# SCH__copy_2024-03-07.net
KiCad netlist of a schematic drawn in EasyEDA
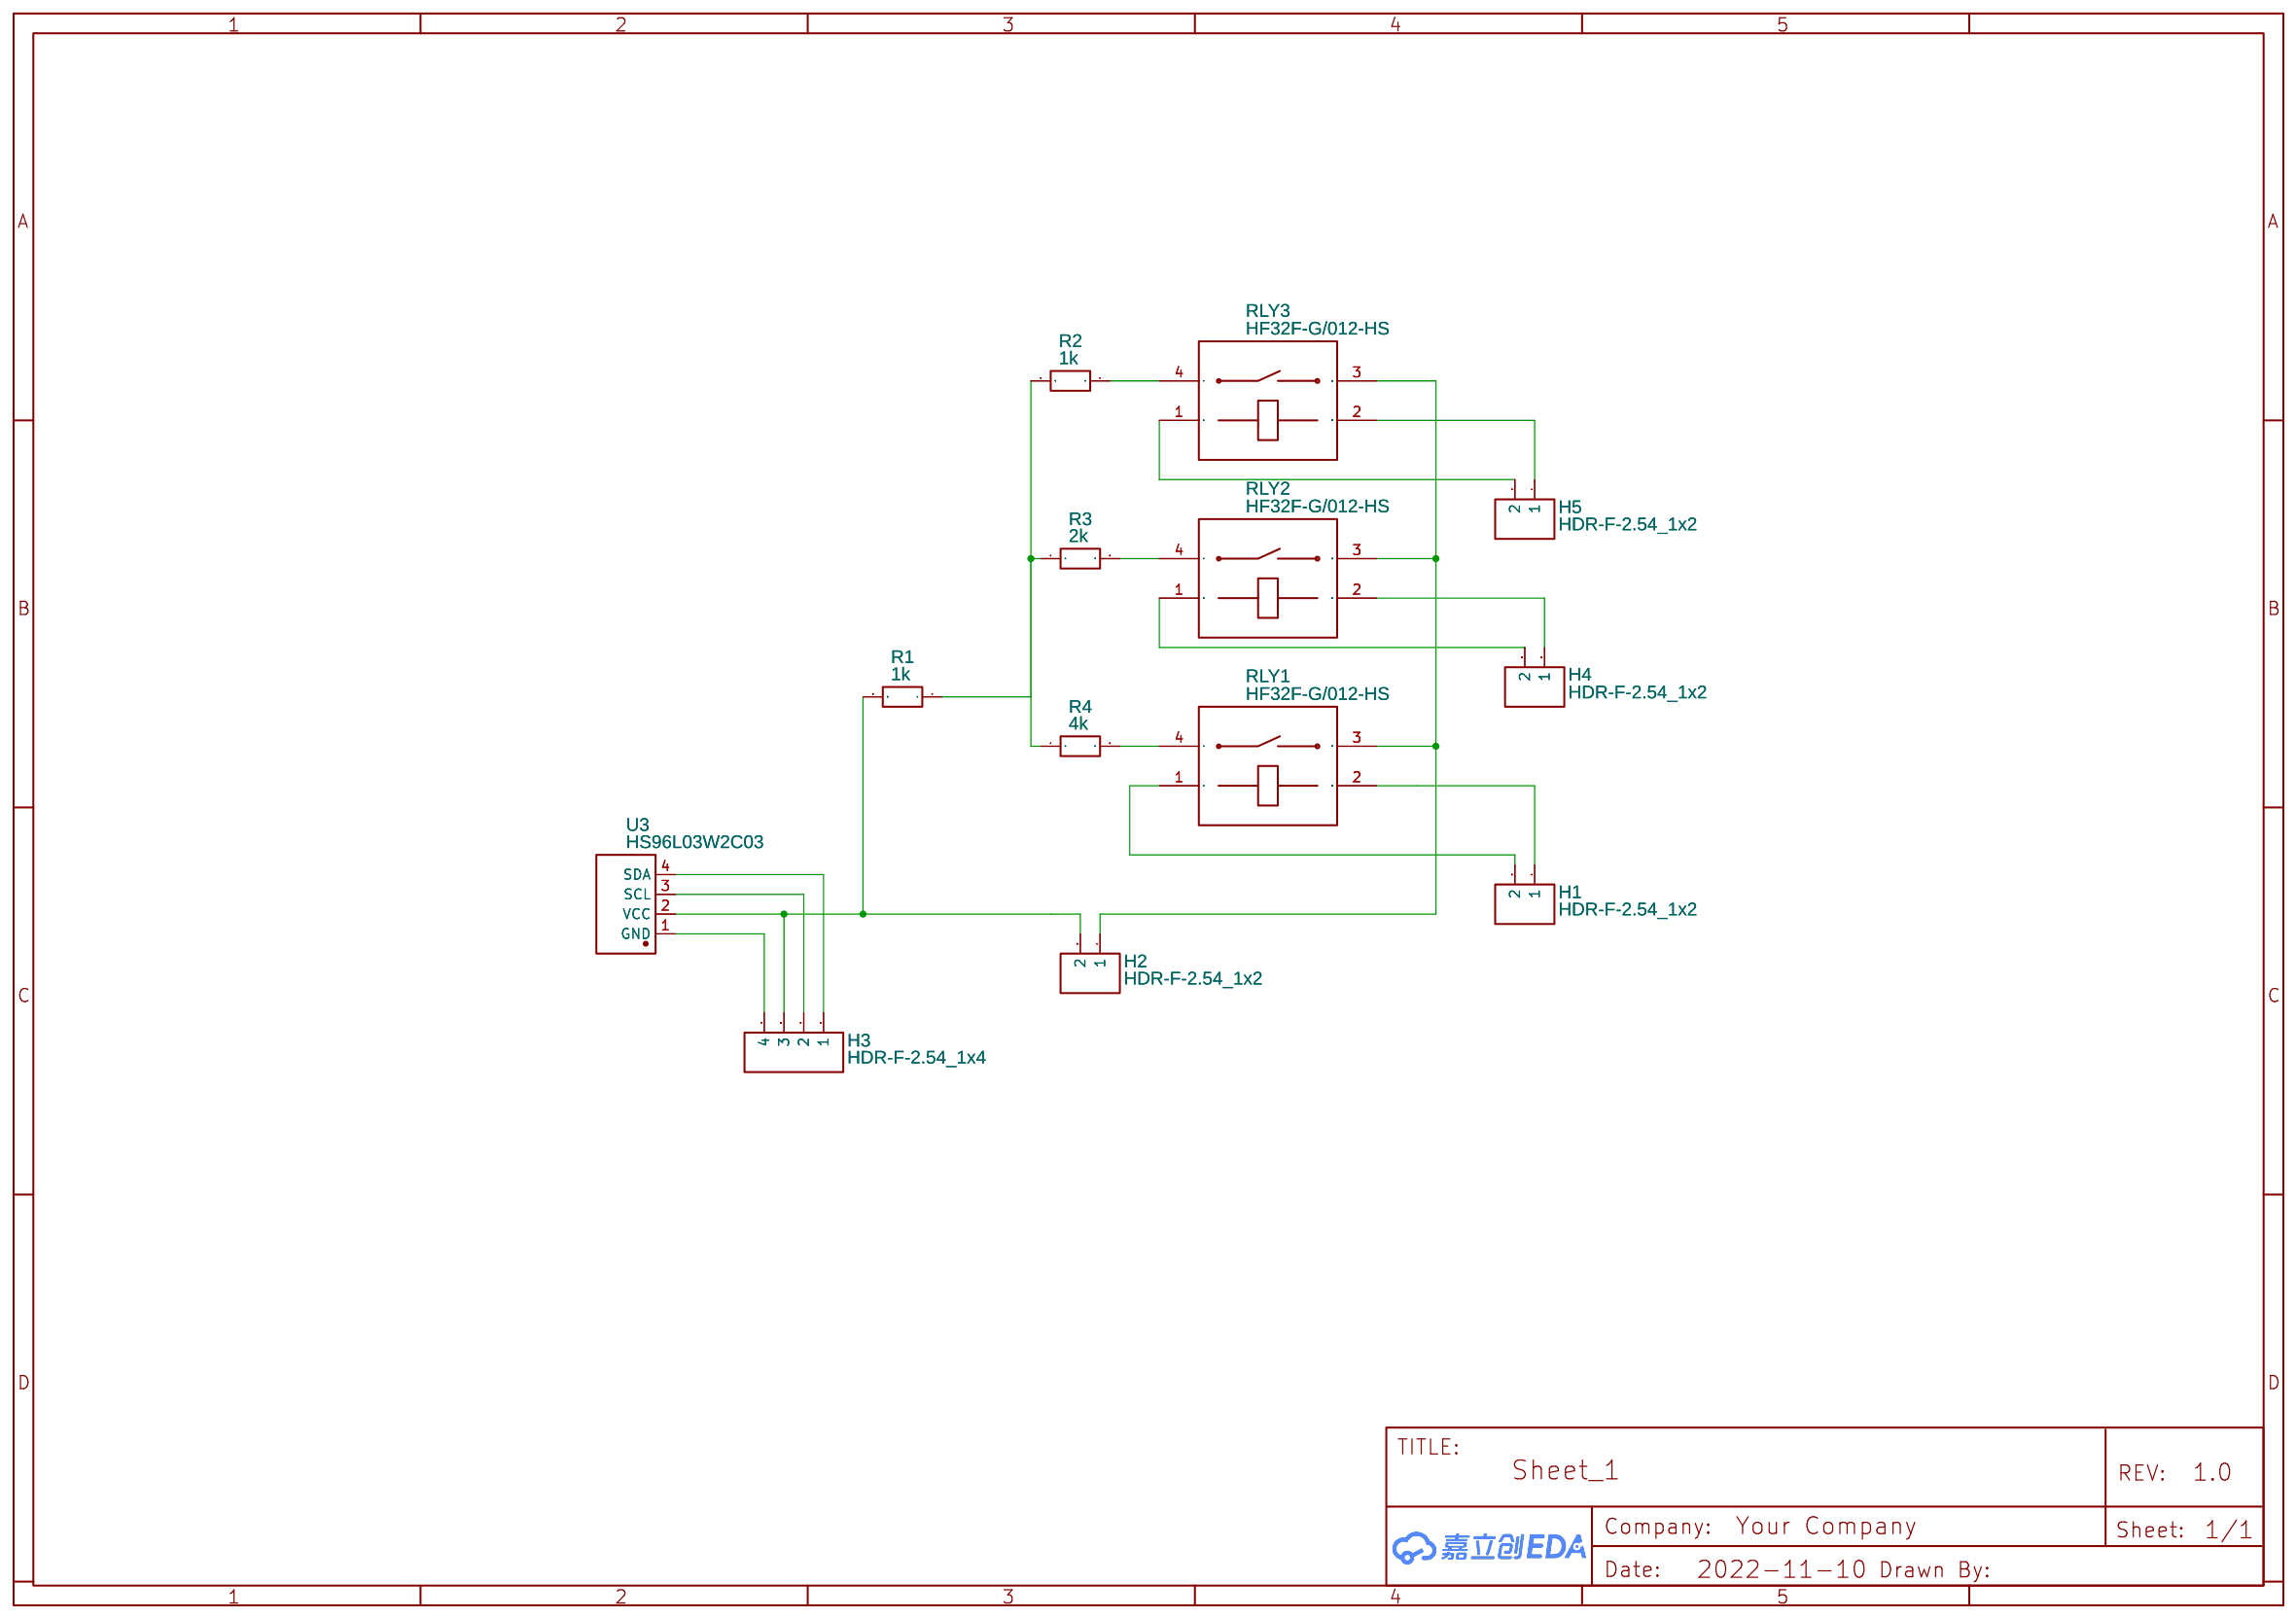
[diagram p0: schematic sheet]

(export (version "E")
  (design (tool "Eeschema 10.0.6"))
  (components
    (comp (ref "H1")
      (value "HDR-F-2.54_1x2")
      (fields (field (name "BOM_Supplier Part") "C49661"))
      (libsource (lib "") (part "HDR-F-2.54_1x2"))
    )
    (comp (ref "H2")
      (value "HDR-F-2.54_1x2")
      (fields (field (name "BOM_Supplier Part") "C49661"))
      (libsource (lib "") (part "HDR-F-2.54_1x2"))
    )
    (comp (ref "H3")
      (value "HDR-F-2.54_1x4")
      (fields (field (name "BOM_Supplier Part") "C225501"))
      (libsource (lib "") (part "HDR-F-2.54_1x4"))
    )
    (comp (ref "H4")
      (value "HDR-F-2.54_1x2")
      (fields (field (name "BOM_Supplier Part") "C49661"))
      (libsource (lib "") (part "HDR-F-2.54_1x2"))
    )
    (comp (ref "H5")
      (value "HDR-F-2.54_1x2")
      (fields (field (name "BOM_Supplier Part") "C49661"))
      (libsource (lib "") (part "HDR-F-2.54_1x2"))
    )
    (comp (ref "R1") (value "1k") (libsource (lib "") (part "R_AXIAL-0.3_EU")))
    (comp (ref "R2") (value "1k") (libsource (lib "") (part "R_AXIAL-0.3_EU")))
    (comp (ref "R3") (value "2k") (libsource (lib "") (part "R_0603_EU")))
    (comp (ref "R4") (value "4k") (libsource (lib "") (part "R_0603_EU")))
    (comp (ref "RLY1")
      (value "HF32F-G/012-HS")
      (fields (field (name "BOM_Supplier Part") "C53562"))
      (libsource (lib "") (part "HF32F-G/012-HS"))
    )
    (comp (ref "RLY2")
      (value "HF32F-G/012-HS")
      (fields (field (name "BOM_Supplier Part") "C53562"))
      (libsource (lib "") (part "HF32F-G/012-HS"))
    )
    (comp (ref "RLY3")
      (value "HF32F-G/012-HS")
      (fields (field (name "BOM_Supplier Part") "C53562"))
      (libsource (lib "") (part "HF32F-G/012-HS"))
    )
    (comp (ref "U3")
      (value "HS96L03W2C03")
      (fields (field (name "BOM_Supplier Part") "C5248080"))
      (libsource (lib "") (part "HS96L03W2C03"))
    )
  )
  (nets
    (net (code "1") (name "Net-(H1-Pad1)") (class "Default")
      (node (ref "H1") (pin "1") (pinfunction "1_1") (pintype "input"))
      (node (ref "RLY1") (pin "2") (pinfunction "2_2") (pintype "input"))
    )
    (net (code "2") (name "Net-(H1-Pad2)") (class "Default")
      (node (ref "H1") (pin "2") (pinfunction "2_2") (pintype "input"))
      (node (ref "RLY1") (pin "1") (pinfunction "1_1") (pintype "input"))
    )
    (net (code "3") (name "Net-(H2-Pad1)") (class "Default")
      (node (ref "H2") (pin "1") (pinfunction "1_1") (pintype "input"))
      (node (ref "RLY1") (pin "3") (pinfunction "3_3") (pintype "input"))
      (node (ref "RLY2") (pin "3") (pinfunction "3_3") (pintype "input"))
      (node (ref "RLY3") (pin "3") (pinfunction "3_3") (pintype "input"))
    )
    (net (code "4") (name "Net-(H4-Pad1)") (class "Default")
      (node (ref "H4") (pin "1") (pinfunction "1_1") (pintype "input"))
      (node (ref "RLY2") (pin "2") (pinfunction "2_2") (pintype "input"))
    )
    (net (code "5") (name "Net-(H4-Pad2)") (class "Default")
      (node (ref "H4") (pin "2") (pinfunction "2_2") (pintype "input"))
      (node (ref "RLY2") (pin "1") (pinfunction "1_1") (pintype "input"))
    )
    (net (code "6") (name "Net-(H5-Pad1)") (class "Default")
      (node (ref "H5") (pin "1") (pinfunction "1_1") (pintype "input"))
      (node (ref "RLY3") (pin "2") (pinfunction "2_2") (pintype "input"))
    )
    (net (code "7") (name "Net-(H5-Pad2)") (class "Default")
      (node (ref "H5") (pin "2") (pinfunction "2_2") (pintype "input"))
      (node (ref "RLY3") (pin "1") (pinfunction "1_1") (pintype "input"))
    )
    (net (code "8") (name "Net-(R1-Pad1)") (class "Default")
      (node (ref "R1") (pin "1") (pinfunction "1_1") (pintype "unspecified"))
      (node (ref "R2") (pin "2") (pinfunction "2_2") (pintype "unspecified"))
      (node (ref "R3") (pin "1") (pinfunction "1_1") (pintype "unspecified"))
      (node (ref "R4") (pin "1") (pinfunction "1_1") (pintype "unspecified"))
    )
    (net (code "9") (name "Net-(R2-Pad1)") (class "Default")
      (node (ref "R2") (pin "1") (pinfunction "1_1") (pintype "unspecified"))
      (node (ref "RLY3") (pin "4") (pinfunction "4_4") (pintype "input"))
    )
    (net (code "10") (name "Net-(R3-Pad2)") (class "Default")
      (node (ref "R3") (pin "2") (pinfunction "2_2") (pintype "unspecified"))
      (node (ref "RLY2") (pin "4") (pinfunction "4_4") (pintype "input"))
    )
    (net (code "11") (name "Net-(R4-Pad2)") (class "Default")
      (node (ref "R4") (pin "2") (pinfunction "2_2") (pintype "unspecified"))
      (node (ref "RLY1") (pin "4") (pinfunction "4_4") (pintype "input"))
    )
    (net (code "12") (name "Net-(U3-GND)") (class "Default")
      (node (ref "H3") (pin "4") (pinfunction "4_4") (pintype "unspecified"))
      (node (ref "U3") (pin "1") (pinfunction "GND_1") (pintype "unspecified"))
    )
    (net (code "13") (name "Net-(U3-SCL)") (class "Default")
      (node (ref "H3") (pin "2") (pinfunction "2_2") (pintype "unspecified"))
      (node (ref "U3") (pin "3") (pinfunction "SCL_3") (pintype "unspecified"))
    )
    (net (code "14") (name "Net-(U3-SDA)") (class "Default")
      (node (ref "H3") (pin "1") (pinfunction "1_1") (pintype "unspecified"))
      (node (ref "U3") (pin "4") (pinfunction "SDA_4") (pintype "unspecified"))
    )
    (net (code "15") (name "Net-(U3-VCC)") (class "Default")
      (node (ref "H2") (pin "2") (pinfunction "2_2") (pintype "input"))
      (node (ref "H3") (pin "3") (pinfunction "3_3") (pintype "unspecified"))
      (node (ref "R1") (pin "2") (pinfunction "2_2") (pintype "unspecified"))
      (node (ref "U3") (pin "2") (pinfunction "VCC_2") (pintype "unspecified"))
    )
  )
)
